# Breakout_to_AHD_Shield.net
KiCad netlist of a schematic drawn in Altium Designer
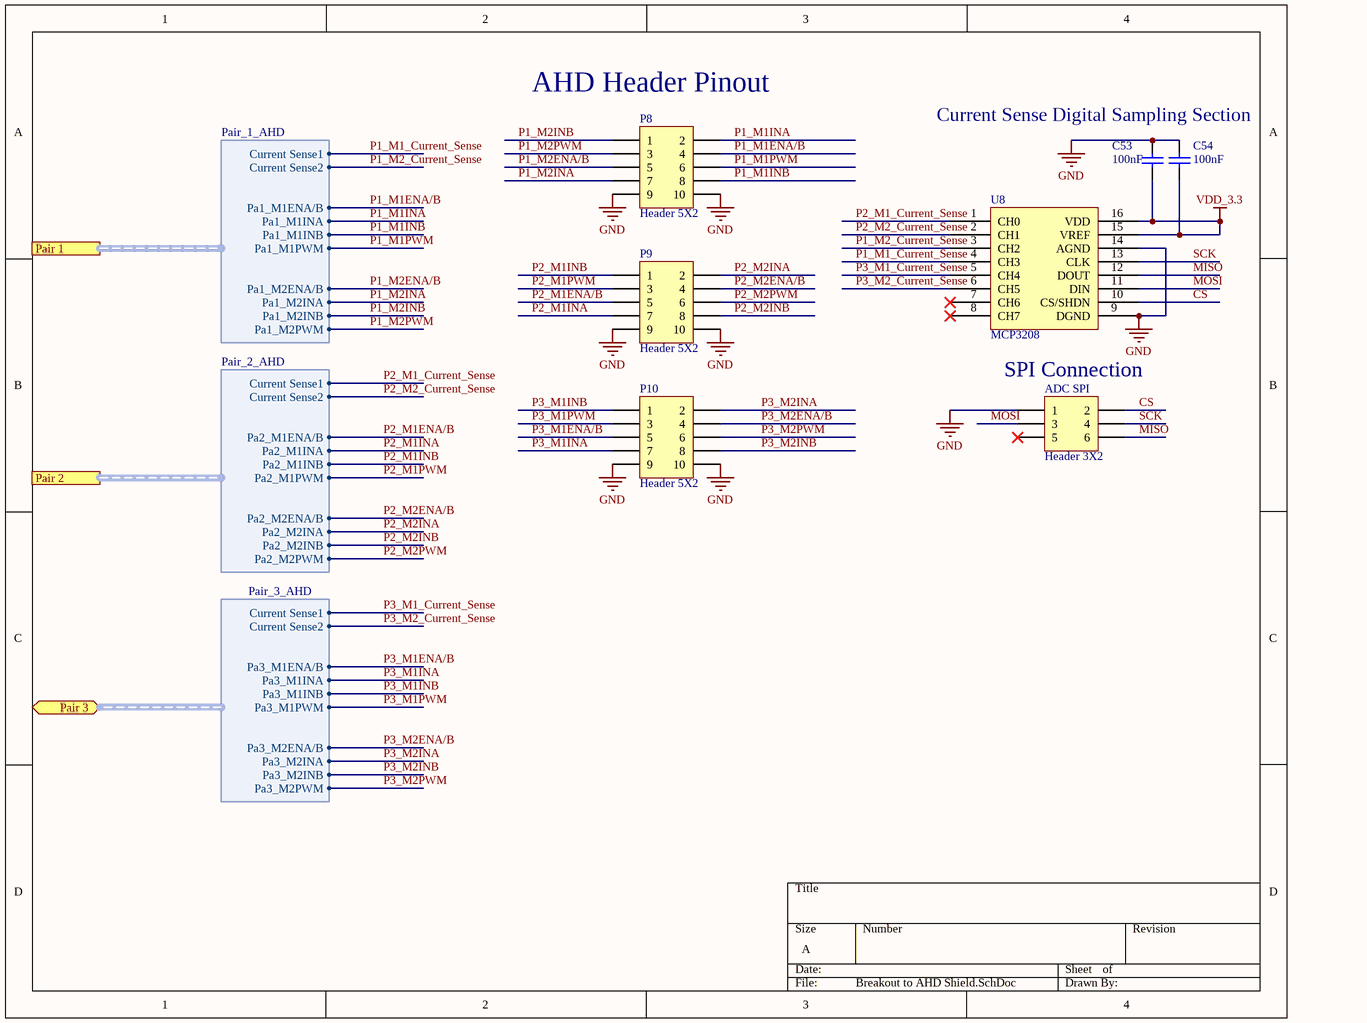
[diagram p0: Breakout to AHD Shield.SchDoc]

(export (version "E")
  (design (tool "Eeschema 10.0.6"))
  (components
    (comp (ref "ADC SPI")
      (value "Header 3X2")
      (footprint "HDR2X3")
      (description "Header, 3-Pin, Dual row")
      (fields (field (name "PUBLISHER") "Altium Limited"))
      (libsource (lib "Miscellaneous Connectors") (part "Header 3X2"))
    )
    (comp (ref "C53")
      (value "100nF")
      (footprint "C1206")
      (description "Capacitor (Semiconductor SIM Model)")
      (fields (field (name "Comment") "Cap Semi") (field (name "PUBLISHER") "Altium Limited"))
      (libsource (lib "Miscellaneous Devices") (part "Cap Semi"))
    )
    (comp (ref "C54")
      (value "100nF")
      (footprint "C1206")
      (description "Capacitor (Semiconductor SIM Model)")
      (fields (field (name "Comment") "Cap Semi") (field (name "PUBLISHER") "Altium Limited"))
      (libsource (lib "Miscellaneous Devices") (part "Cap Semi"))
    )
    (comp (ref "P8")
      (value "Header 5X2")
      (footprint "HDR2X5")
      (description "Header, 5-Pin, Dual row")
      (fields (field (name "PUBLISHER") "Altium Limited"))
      (libsource (lib "Miscellaneous Connectors") (part "Header 5X2"))
    )
    (comp (ref "P9")
      (value "Header 5X2")
      (footprint "HDR2X5")
      (description "Header, 5-Pin, Dual row")
      (fields (field (name "PUBLISHER") "Altium Limited"))
      (libsource (lib "Miscellaneous Connectors") (part "Header 5X2"))
    )
    (comp (ref "P10")
      (value "Header 5X2")
      (footprint "HDR2X5")
      (description "Header, 5-Pin, Dual row")
      (fields (field (name "PUBLISHER") "Altium Limited"))
      (libsource (lib "Miscellaneous Connectors") (part "Header 5X2"))
    )
    (comp (ref "U8")
      (value "MCP3208")
      (footprint "MCP3208 - duplicate")
      (libsource (lib "Power Distribution Board") (part "MCP3208"))
    )
  )
  (nets
    (net (code "4") (name "/CS") (class "Default")
      (node (ref "ADC SPI") (pin "2") (pinfunction "2_2") (pintype "passive"))
      (node (ref "U8") (pin "10") (pinfunction "CS/SHDN_10") (pintype "passive"))
    )
    (net (code "5") (name "/MISO") (class "Default")
      (node (ref "ADC SPI") (pin "6") (pinfunction "6_6") (pintype "passive"))
      (node (ref "U8") (pin "12") (pinfunction "DOUT_12") (pintype "passive"))
    )
    (net (code "6") (name "/MOSI") (class "Default")
      (node (ref "ADC SPI") (pin "3") (pinfunction "3_3") (pintype "passive"))
      (node (ref "U8") (pin "11") (pinfunction "DIN_11") (pintype "passive"))
    )
    (net (code "7") (name "/P1_M1ENA{slash}B") (class "Default")
      (node (ref "P8") (pin "4") (pinfunction "4_4") (pintype "passive"))
    )
    (net (code "8") (name "/P1_M1INA") (class "Default")
      (node (ref "P8") (pin "2") (pinfunction "2_2") (pintype "passive"))
    )
    (net (code "9") (name "/P1_M1INB") (class "Default")
      (node (ref "P8") (pin "8") (pinfunction "8_8") (pintype "passive"))
    )
    (net (code "10") (name "/P1_M1PWM") (class "Default")
      (node (ref "P8") (pin "6") (pinfunction "6_6") (pintype "passive"))
    )
    (net (code "11") (name "/P1_M1_Current_Sense") (class "Default")
      (node (ref "U8") (pin "4") (pinfunction "CH3_4") (pintype "passive"))
    )
    (net (code "12") (name "/P1_M2ENA{slash}B") (class "Default")
      (node (ref "P8") (pin "5") (pinfunction "5_5") (pintype "passive"))
    )
    (net (code "13") (name "/P1_M2INA") (class "Default")
      (node (ref "P8") (pin "7") (pinfunction "7_7") (pintype "passive"))
    )
    (net (code "14") (name "/P1_M2INB") (class "Default")
      (node (ref "P8") (pin "1") (pinfunction "1_1") (pintype "passive"))
    )
    (net (code "15") (name "/P1_M2PWM") (class "Default")
      (node (ref "P8") (pin "3") (pinfunction "3_3") (pintype "passive"))
    )
    (net (code "16") (name "/P1_M2_Current_Sense") (class "Default")
      (node (ref "U8") (pin "3") (pinfunction "CH2_3") (pintype "passive"))
    )
    (net (code "17") (name "/P2_M1ENA{slash}B") (class "Default")
      (node (ref "P9") (pin "5") (pinfunction "5_5") (pintype "passive"))
    )
    (net (code "18") (name "/P2_M1INA") (class "Default")
      (node (ref "P9") (pin "7") (pinfunction "7_7") (pintype "passive"))
    )
    (net (code "19") (name "/P2_M1INB") (class "Default")
      (node (ref "P9") (pin "1") (pinfunction "1_1") (pintype "passive"))
    )
    (net (code "20") (name "/P2_M1PWM") (class "Default")
      (node (ref "P9") (pin "3") (pinfunction "3_3") (pintype "passive"))
    )
    (net (code "21") (name "/P2_M1_Current_Sense") (class "Default")
      (node (ref "U8") (pin "1") (pinfunction "CH0_1") (pintype "passive"))
    )
    (net (code "22") (name "/P2_M2ENA{slash}B") (class "Default")
      (node (ref "P9") (pin "4") (pinfunction "4_4") (pintype "passive"))
    )
    (net (code "23") (name "/P2_M2INA") (class "Default")
      (node (ref "P9") (pin "2") (pinfunction "2_2") (pintype "passive"))
    )
    (net (code "24") (name "/P2_M2INB") (class "Default")
      (node (ref "P9") (pin "8") (pinfunction "8_8") (pintype "passive"))
    )
    (net (code "25") (name "/P2_M2PWM") (class "Default")
      (node (ref "P9") (pin "6") (pinfunction "6_6") (pintype "passive"))
    )
    (net (code "26") (name "/P2_M2_Current_Sense") (class "Default")
      (node (ref "U8") (pin "2") (pinfunction "CH1_2") (pintype "passive"))
    )
    (net (code "27") (name "/P3_M1ENA{slash}B") (class "Default")
      (node (ref "P10") (pin "5") (pinfunction "5_5") (pintype "passive"))
    )
    (net (code "28") (name "/P3_M1INA") (class "Default")
      (node (ref "P10") (pin "7") (pinfunction "7_7") (pintype "passive"))
    )
    (net (code "29") (name "/P3_M1INB") (class "Default")
      (node (ref "P10") (pin "1") (pinfunction "1_1") (pintype "passive"))
    )
    (net (code "30") (name "/P3_M1PWM") (class "Default")
      (node (ref "P10") (pin "3") (pinfunction "3_3") (pintype "passive"))
    )
    (net (code "31") (name "/P3_M1_Current_Sense") (class "Default")
      (node (ref "U8") (pin "5") (pinfunction "CH4_5") (pintype "passive"))
    )
    (net (code "32") (name "/P3_M2ENA{slash}B") (class "Default")
      (node (ref "P10") (pin "4") (pinfunction "4_4") (pintype "passive"))
    )
    (net (code "33") (name "/P3_M2INA") (class "Default")
      (node (ref "P10") (pin "2") (pinfunction "2_2") (pintype "passive"))
    )
    (net (code "34") (name "/P3_M2INB") (class "Default")
      (node (ref "P10") (pin "8") (pinfunction "8_8") (pintype "passive"))
    )
    (net (code "35") (name "/P3_M2PWM") (class "Default")
      (node (ref "P10") (pin "6") (pinfunction "6_6") (pintype "passive"))
    )
    (net (code "36") (name "/P3_M2_Current_Sense") (class "Default")
      (node (ref "U8") (pin "6") (pinfunction "CH5_6") (pintype "passive"))
    )
    (net (code "37") (name "/SCK") (class "Default")
      (node (ref "ADC SPI") (pin "4") (pinfunction "4_4") (pintype "passive"))
      (node (ref "U8") (pin "13") (pinfunction "CLK_13") (pintype "passive"))
    )
    (net (code "41") (name "GND") (class "Default")
      (node (ref "ADC SPI") (pin "1") (pinfunction "1_1") (pintype "passive"))
      (node (ref "C53") (pin "2") (pinfunction "2_2") (pintype "passive"))
      (node (ref "C54") (pin "2") (pinfunction "2_2") (pintype "passive"))
      (node (ref "P10") (pin "10") (pinfunction "10_10") (pintype "passive"))
      (node (ref "P10") (pin "9") (pinfunction "9_9") (pintype "passive"))
      (node (ref "P8") (pin "10") (pinfunction "10_10") (pintype "passive"))
      (node (ref "P8") (pin "9") (pinfunction "9_9") (pintype "passive"))
      (node (ref "P9") (pin "10") (pinfunction "10_10") (pintype "passive"))
      (node (ref "P9") (pin "9") (pinfunction "9_9") (pintype "passive"))
      (node (ref "U8") (pin "14") (pinfunction "AGND_14") (pintype "passive"))
      (node (ref "U8") (pin "9") (pinfunction "DGND_9") (pintype "passive"))
    )
    (net (code "42") (name "VDD_3.3") (class "Default")
      (node (ref "C53") (pin "1") (pinfunction "1_1") (pintype "passive"))
      (node (ref "C54") (pin "1") (pinfunction "1_1") (pintype "passive"))
      (node (ref "U8") (pin "15") (pinfunction "VREF_15") (pintype "passive"))
      (node (ref "U8") (pin "16") (pinfunction "VDD_16") (pintype "passive"))
    )
    (net (code "43") (name "unconnected-(ADC SPI-Pad5)") (class "Default")
      (node (ref "ADC SPI") (pin "5") (pinfunction "5_5") (pintype "passive+no_connect"))
    )
    (net (code "44") (name "unconnected-(U8-CH6-Pad7)") (class "Default")
      (node (ref "U8") (pin "7") (pinfunction "CH6_7") (pintype "passive+no_connect"))
    )
    (net (code "45") (name "unconnected-(U8-CH7-Pad8)") (class "Default")
      (node (ref "U8") (pin "8") (pinfunction "CH7_8") (pintype "passive+no_connect"))
    )
  )
)
